# Attenuator.net
KiCad netlist of a schematic drawn in EAGLE
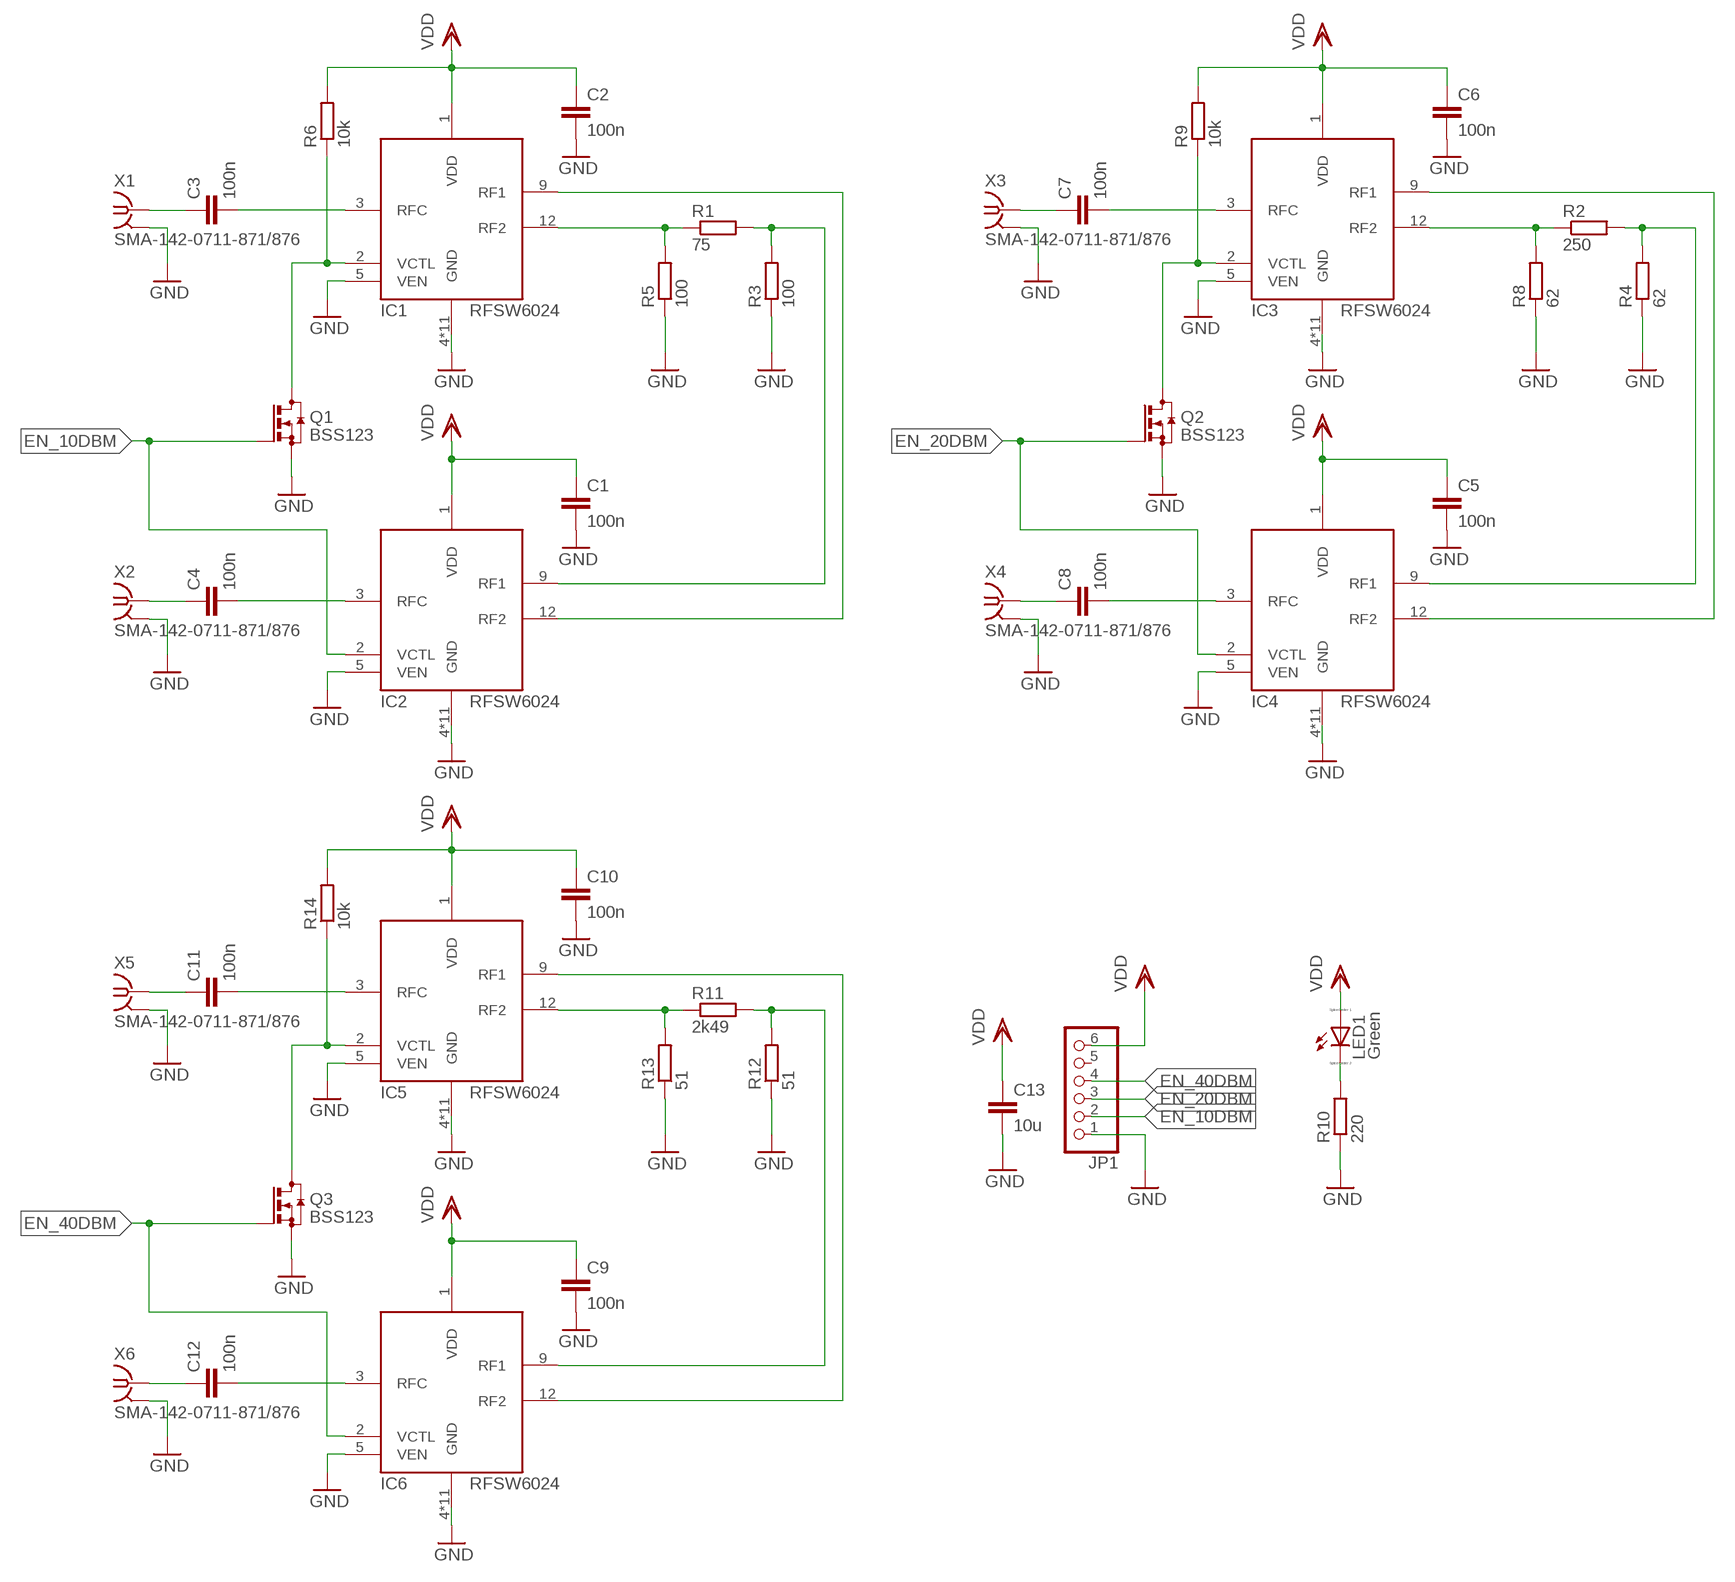
[diagram p0: schematic, sheet 1]

(export (version "E")
  (design (tool "Eeschema 10.0.6"))
  (components
    (comp (ref "C1")
      (value "100n")
      (footprint "eagle-import:C0603K")
      (libsource (lib "eagle-import") (part "rcl_334_C-EUC0603K"))
    )
    (comp (ref "C2")
      (value "100n")
      (footprint "eagle-import:C0603K")
      (libsource (lib "eagle-import") (part "rcl_334_C-EUC0603K"))
    )
    (comp (ref "C3")
      (value "100n")
      (footprint "eagle-import:C0603K")
      (libsource (lib "eagle-import") (part "rcl_334_C-EUC0603K"))
    )
    (comp (ref "C4")
      (value "100n")
      (footprint "eagle-import:C0603K")
      (libsource (lib "eagle-import") (part "rcl_334_C-EUC0603K"))
    )
    (comp (ref "C5")
      (value "100n")
      (footprint "eagle-import:C0603K")
      (libsource (lib "eagle-import") (part "rcl_334_C-EUC0603K"))
    )
    (comp (ref "C6")
      (value "100n")
      (footprint "eagle-import:C0603K")
      (libsource (lib "eagle-import") (part "rcl_334_C-EUC0603K"))
    )
    (comp (ref "C7")
      (value "100n")
      (footprint "eagle-import:C0603K")
      (libsource (lib "eagle-import") (part "rcl_334_C-EUC0603K"))
    )
    (comp (ref "C8")
      (value "100n")
      (footprint "eagle-import:C0603K")
      (libsource (lib "eagle-import") (part "rcl_334_C-EUC0603K"))
    )
    (comp (ref "C9")
      (value "100n")
      (footprint "eagle-import:C0603K")
      (libsource (lib "eagle-import") (part "rcl_334_C-EUC0603K"))
    )
    (comp (ref "C10")
      (value "100n")
      (footprint "eagle-import:C0603K")
      (libsource (lib "eagle-import") (part "rcl_334_C-EUC0603K"))
    )
    (comp (ref "C11")
      (value "100n")
      (footprint "eagle-import:C0603K")
      (libsource (lib "eagle-import") (part "rcl_334_C-EUC0603K"))
    )
    (comp (ref "C12")
      (value "100n")
      (footprint "eagle-import:C0603K")
      (libsource (lib "eagle-import") (part "rcl_334_C-EUC0603K"))
    )
    (comp (ref "C13")
      (value "10u")
      (footprint "eagle-import:C1206")
      (libsource (lib "eagle-import") (part "C-EUC1206"))
    )
    (comp (ref "IC1")
      (value "RFSW6024")
      (footprint "eagle-import:QFN16")
      (libsource (lib "eagle-import") (part "RFSW6024"))
    )
    (comp (ref "IC2")
      (value "RFSW6024")
      (footprint "eagle-import:QFN16")
      (libsource (lib "eagle-import") (part "RFSW6024"))
    )
    (comp (ref "IC3")
      (value "RFSW6024")
      (footprint "eagle-import:QFN16")
      (libsource (lib "eagle-import") (part "RFSW6024"))
    )
    (comp (ref "IC4")
      (value "RFSW6024")
      (footprint "eagle-import:QFN16")
      (libsource (lib "eagle-import") (part "RFSW6024"))
    )
    (comp (ref "IC5")
      (value "RFSW6024")
      (footprint "eagle-import:QFN16")
      (libsource (lib "eagle-import") (part "RFSW6024"))
    )
    (comp (ref "IC6")
      (value "RFSW6024")
      (footprint "eagle-import:QFN16")
      (libsource (lib "eagle-import") (part "RFSW6024"))
    )
    (comp (ref "JP1")
      (value "PINHD-1X6/90")
      (footprint "eagle-import:1X06_90")
      (libsource (lib "eagle-import") (part "PINHD-1X6/90"))
    )
    (comp (ref "LED1")
      (value "Green")
      (footprint "eagle-import:LED_SML0603")
      (libsource (lib "eagle-import") (part "LED_ESML0603"))
    )
    (comp (ref "Q1")
      (value "BSS123")
      (footprint "eagle-import:SOT23")
      (libsource (lib "eagle-import") (part "BSS123"))
    )
    (comp (ref "Q2")
      (value "BSS123")
      (footprint "eagle-import:SOT23")
      (libsource (lib "eagle-import") (part "BSS123"))
    )
    (comp (ref "Q3")
      (value "BSS123")
      (footprint "eagle-import:SOT23")
      (libsource (lib "eagle-import") (part "BSS123"))
    )
    (comp (ref "R1")
      (value "75")
      (footprint "eagle-import:R0603")
      (libsource (lib "eagle-import") (part "resistor_348_R-EU_R0603"))
    )
    (comp (ref "R2")
      (value "250")
      (footprint "eagle-import:R0603")
      (libsource (lib "eagle-import") (part "resistor_348_R-EU_R0603"))
    )
    (comp (ref "R3")
      (value "100")
      (footprint "eagle-import:R0603")
      (libsource (lib "eagle-import") (part "resistor_348_R-EU_R0603"))
    )
    (comp (ref "R4")
      (value "62")
      (footprint "eagle-import:R0603")
      (libsource (lib "eagle-import") (part "resistor_348_R-EU_R0603"))
    )
    (comp (ref "R5")
      (value "100")
      (footprint "eagle-import:R0603")
      (libsource (lib "eagle-import") (part "resistor_348_R-EU_R0603"))
    )
    (comp (ref "R6")
      (value "10k")
      (footprint "eagle-import:R0603")
      (libsource (lib "eagle-import") (part "resistor_348_R-EU_R0603"))
    )
    (comp (ref "R8")
      (value "62")
      (footprint "eagle-import:R0603")
      (libsource (lib "eagle-import") (part "resistor_348_R-EU_R0603"))
    )
    (comp (ref "R9")
      (value "10k")
      (footprint "eagle-import:R0603")
      (libsource (lib "eagle-import") (part "resistor_348_R-EU_R0603"))
    )
    (comp (ref "R10")
      (value "220")
      (footprint "eagle-import:R0603")
      (libsource (lib "eagle-import") (part "R-EU_R0603"))
    )
    (comp (ref "R11")
      (value "2k49")
      (footprint "eagle-import:R0603")
      (libsource (lib "eagle-import") (part "resistor_348_R-EU_R0603"))
    )
    (comp (ref "R12")
      (value "51")
      (footprint "eagle-import:R0603")
      (libsource (lib "eagle-import") (part "resistor_348_R-EU_R0603"))
    )
    (comp (ref "R13")
      (value "51")
      (footprint "eagle-import:R0603")
      (libsource (lib "eagle-import") (part "resistor_348_R-EU_R0603"))
    )
    (comp (ref "R14")
      (value "10k")
      (footprint "eagle-import:R0603")
      (libsource (lib "eagle-import") (part "resistor_348_R-EU_R0603"))
    )
    (comp (ref "X1")
      (value "SMA-142-0711-871/876")
      (footprint "eagle-import:J502-ND-142-0711-871_876")
      (fields (field (name "MF") "JOHNSON COMPONENTS") (field (name "MPN") "142-0711-871"))
      (libsource (lib "eagle-import") (part "SMA-142-0711-871/876"))
    )
    (comp (ref "X2")
      (value "SMA-142-0711-871/876")
      (footprint "eagle-import:J502-ND-142-0711-871_876")
      (fields (field (name "MF") "JOHNSON COMPONENTS") (field (name "MPN") "142-0711-871"))
      (libsource (lib "eagle-import") (part "SMA-142-0711-871/876"))
    )
    (comp (ref "X3")
      (value "SMA-142-0711-871/876")
      (footprint "eagle-import:J502-ND-142-0711-871_876")
      (fields (field (name "MF") "JOHNSON COMPONENTS") (field (name "MPN") "142-0711-871"))
      (libsource (lib "eagle-import") (part "SMA-142-0711-871/876"))
    )
    (comp (ref "X4")
      (value "SMA-142-0711-871/876")
      (footprint "eagle-import:J502-ND-142-0711-871_876")
      (fields (field (name "MF") "JOHNSON COMPONENTS") (field (name "MPN") "142-0711-871"))
      (libsource (lib "eagle-import") (part "SMA-142-0711-871/876"))
    )
    (comp (ref "X5")
      (value "SMA-142-0711-871/876")
      (footprint "eagle-import:J502-ND-142-0711-871_876")
      (fields (field (name "MF") "JOHNSON COMPONENTS") (field (name "MPN") "142-0711-871"))
      (libsource (lib "eagle-import") (part "SMA-142-0711-871/876"))
    )
    (comp (ref "X6")
      (value "SMA-142-0711-871/876")
      (footprint "eagle-import:J502-ND-142-0711-871_876")
      (fields (field (name "MF") "JOHNSON COMPONENTS") (field (name "MPN") "142-0711-871"))
      (libsource (lib "eagle-import") (part "SMA-142-0711-871/876"))
    )
  )
  (nets
    (net (code "1") (name "EN_10DBM") (class "Default")
      (node (ref "IC2") (pin "2") (pinfunction "VCTL_2") (pintype "bidirectional"))
      (node (ref "JP1") (pin "2") (pinfunction "2_2") (pintype "passive"))
      (node (ref "Q1") (pin "1") (pinfunction "G_1") (pintype "passive"))
    )
    (net (code "2") (name "EN_20DBM") (class "Default")
      (node (ref "IC4") (pin "2") (pinfunction "VCTL_2") (pintype "bidirectional"))
      (node (ref "JP1") (pin "3") (pinfunction "3_3") (pintype "passive"))
      (node (ref "Q2") (pin "1") (pinfunction "G_1") (pintype "passive"))
    )
    (net (code "3") (name "EN_40DBM") (class "Default")
      (node (ref "IC6") (pin "2") (pinfunction "VCTL_2") (pintype "bidirectional"))
      (node (ref "JP1") (pin "4") (pinfunction "4_4") (pintype "passive"))
      (node (ref "Q3") (pin "1") (pinfunction "G_1") (pintype "passive"))
    )
    (net (code "4") (name "GND") (class "Default")
      (node (ref "C1") (pin "2") (pinfunction "2_2") (pintype "passive"))
      (node (ref "C10") (pin "2") (pinfunction "2_2") (pintype "passive"))
      (node (ref "C13") (pin "2") (pinfunction "2_2") (pintype "passive"))
      (node (ref "C2") (pin "2") (pinfunction "2_2") (pintype "passive"))
      (node (ref "C5") (pin "2") (pinfunction "2_2") (pintype "passive"))
      (node (ref "C6") (pin "2") (pinfunction "2_2") (pintype "passive"))
      (node (ref "C9") (pin "2") (pinfunction "2_2") (pintype "passive"))
      (node (ref "IC1") (pin "10") (pinfunction "GND_10") (pintype "bidirectional"))
      (node (ref "IC1") (pin "11") (pinfunction "GND_11") (pintype "bidirectional"))
      (node (ref "IC1") (pin "13") (pinfunction "GND_13") (pintype "bidirectional"))
      (node (ref "IC1") (pin "14") (pinfunction "GND_14") (pintype "bidirectional"))
      (node (ref "IC1") (pin "15") (pinfunction "GND_15") (pintype "bidirectional"))
      (node (ref "IC1") (pin "16") (pinfunction "GND_16") (pintype "bidirectional"))
      (node (ref "IC1") (pin "17") (pinfunction "GND_17") (pintype "bidirectional"))
      (node (ref "IC1") (pin "4") (pinfunction "GND_4") (pintype "bidirectional"))
      (node (ref "IC1") (pin "5") (pinfunction "VEN_5") (pintype "bidirectional"))
      (node (ref "IC1") (pin "6") (pinfunction "GND_6") (pintype "bidirectional"))
      (node (ref "IC1") (pin "7") (pinfunction "GND_7") (pintype "bidirectional"))
      (node (ref "IC1") (pin "8") (pinfunction "GND_8") (pintype "bidirectional"))
      (node (ref "IC2") (pin "10") (pinfunction "GND_10") (pintype "bidirectional"))
      (node (ref "IC2") (pin "11") (pinfunction "GND_11") (pintype "bidirectional"))
      (node (ref "IC2") (pin "13") (pinfunction "GND_13") (pintype "bidirectional"))
      (node (ref "IC2") (pin "14") (pinfunction "GND_14") (pintype "bidirectional"))
      (node (ref "IC2") (pin "15") (pinfunction "GND_15") (pintype "bidirectional"))
      (node (ref "IC2") (pin "16") (pinfunction "GND_16") (pintype "bidirectional"))
      (node (ref "IC2") (pin "17") (pinfunction "GND_17") (pintype "bidirectional"))
      (node (ref "IC2") (pin "4") (pinfunction "GND_4") (pintype "bidirectional"))
      (node (ref "IC2") (pin "5") (pinfunction "VEN_5") (pintype "bidirectional"))
      (node (ref "IC2") (pin "6") (pinfunction "GND_6") (pintype "bidirectional"))
      (node (ref "IC2") (pin "7") (pinfunction "GND_7") (pintype "bidirectional"))
      (node (ref "IC2") (pin "8") (pinfunction "GND_8") (pintype "bidirectional"))
      (node (ref "IC3") (pin "10") (pinfunction "GND_10") (pintype "bidirectional"))
      (node (ref "IC3") (pin "11") (pinfunction "GND_11") (pintype "bidirectional"))
      (node (ref "IC3") (pin "13") (pinfunction "GND_13") (pintype "bidirectional"))
      (node (ref "IC3") (pin "14") (pinfunction "GND_14") (pintype "bidirectional"))
      (node (ref "IC3") (pin "15") (pinfunction "GND_15") (pintype "bidirectional"))
      (node (ref "IC3") (pin "16") (pinfunction "GND_16") (pintype "bidirectional"))
      (node (ref "IC3") (pin "17") (pinfunction "GND_17") (pintype "bidirectional"))
      (node (ref "IC3") (pin "4") (pinfunction "GND_4") (pintype "bidirectional"))
      (node (ref "IC3") (pin "5") (pinfunction "VEN_5") (pintype "bidirectional"))
      (node (ref "IC3") (pin "6") (pinfunction "GND_6") (pintype "bidirectional"))
      (node (ref "IC3") (pin "7") (pinfunction "GND_7") (pintype "bidirectional"))
      (node (ref "IC3") (pin "8") (pinfunction "GND_8") (pintype "bidirectional"))
      (node (ref "IC4") (pin "10") (pinfunction "GND_10") (pintype "bidirectional"))
      (node (ref "IC4") (pin "11") (pinfunction "GND_11") (pintype "bidirectional"))
      (node (ref "IC4") (pin "13") (pinfunction "GND_13") (pintype "bidirectional"))
      (node (ref "IC4") (pin "14") (pinfunction "GND_14") (pintype "bidirectional"))
      (node (ref "IC4") (pin "15") (pinfunction "GND_15") (pintype "bidirectional"))
      (node (ref "IC4") (pin "16") (pinfunction "GND_16") (pintype "bidirectional"))
      (node (ref "IC4") (pin "17") (pinfunction "GND_17") (pintype "bidirectional"))
      (node (ref "IC4") (pin "4") (pinfunction "GND_4") (pintype "bidirectional"))
      (node (ref "IC4") (pin "5") (pinfunction "VEN_5") (pintype "bidirectional"))
      (node (ref "IC4") (pin "6") (pinfunction "GND_6") (pintype "bidirectional"))
      (node (ref "IC4") (pin "7") (pinfunction "GND_7") (pintype "bidirectional"))
      (node (ref "IC4") (pin "8") (pinfunction "GND_8") (pintype "bidirectional"))
      (node (ref "IC5") (pin "10") (pinfunction "GND_10") (pintype "bidirectional"))
      (node (ref "IC5") (pin "11") (pinfunction "GND_11") (pintype "bidirectional"))
      (node (ref "IC5") (pin "13") (pinfunction "GND_13") (pintype "bidirectional"))
      (node (ref "IC5") (pin "14") (pinfunction "GND_14") (pintype "bidirectional"))
      (node (ref "IC5") (pin "15") (pinfunction "GND_15") (pintype "bidirectional"))
      (node (ref "IC5") (pin "16") (pinfunction "GND_16") (pintype "bidirectional"))
      (node (ref "IC5") (pin "17") (pinfunction "GND_17") (pintype "bidirectional"))
      (node (ref "IC5") (pin "4") (pinfunction "GND_4") (pintype "bidirectional"))
      (node (ref "IC5") (pin "5") (pinfunction "VEN_5") (pintype "bidirectional"))
      (node (ref "IC5") (pin "6") (pinfunction "GND_6") (pintype "bidirectional"))
      (node (ref "IC5") (pin "7") (pinfunction "GND_7") (pintype "bidirectional"))
      (node (ref "IC5") (pin "8") (pinfunction "GND_8") (pintype "bidirectional"))
      (node (ref "IC6") (pin "10") (pinfunction "GND_10") (pintype "bidirectional"))
      (node (ref "IC6") (pin "11") (pinfunction "GND_11") (pintype "bidirectional"))
      (node (ref "IC6") (pin "13") (pinfunction "GND_13") (pintype "bidirectional"))
      (node (ref "IC6") (pin "14") (pinfunction "GND_14") (pintype "bidirectional"))
      (node (ref "IC6") (pin "15") (pinfunction "GND_15") (pintype "bidirectional"))
      (node (ref "IC6") (pin "16") (pinfunction "GND_16") (pintype "bidirectional"))
      (node (ref "IC6") (pin "17") (pinfunction "GND_17") (pintype "bidirectional"))
      (node (ref "IC6") (pin "4") (pinfunction "GND_4") (pintype "bidirectional"))
      (node (ref "IC6") (pin "5") (pinfunction "VEN_5") (pintype "bidirectional"))
      (node (ref "IC6") (pin "6") (pinfunction "GND_6") (pintype "bidirectional"))
      (node (ref "IC6") (pin "7") (pinfunction "GND_7") (pintype "bidirectional"))
      (node (ref "IC6") (pin "8") (pinfunction "GND_8") (pintype "bidirectional"))
      (node (ref "JP1") (pin "1") (pinfunction "1_1") (pintype "passive"))
      (node (ref "Q1") (pin "2") (pinfunction "S_2") (pintype "passive"))
      (node (ref "Q2") (pin "2") (pinfunction "S_2") (pintype "passive"))
      (node (ref "Q3") (pin "2") (pinfunction "S_2") (pintype "passive"))
      (node (ref "R10") (pin "1") (pinfunction "1_1") (pintype "passive"))
      (node (ref "R12") (pin "1") (pinfunction "1_1") (pintype "passive"))
      (node (ref "R13") (pin "1") (pinfunction "1_1") (pintype "passive"))
      (node (ref "R3") (pin "1") (pinfunction "1_1") (pintype "passive"))
      (node (ref "R4") (pin "1") (pinfunction "1_1") (pintype "passive"))
      (node (ref "R5") (pin "1") (pinfunction "1_1") (pintype "passive"))
      (node (ref "R8") (pin "1") (pinfunction "1_1") (pintype "passive"))
      (node (ref "X1") (pin "G@1") (pinfunction "2_G@1") (pintype "passive"))
      (node (ref "X1") (pin "G@2") (pinfunction "2_G@2") (pintype "passive"))
      (node (ref "X1") (pin "G@3") (pinfunction "2_G@3") (pintype "passive"))
      (node (ref "X1") (pin "G@4") (pinfunction "2_G@4") (pintype "passive"))
      (node (ref "X2") (pin "G@1") (pinfunction "2_G@1") (pintype "passive"))
      (node (ref "X2") (pin "G@2") (pinfunction "2_G@2") (pintype "passive"))
      (node (ref "X2") (pin "G@3") (pinfunction "2_G@3") (pintype "passive"))
      (node (ref "X2") (pin "G@4") (pinfunction "2_G@4") (pintype "passive"))
      (node (ref "X3") (pin "G@1") (pinfunction "2_G@1") (pintype "passive"))
      (node (ref "X3") (pin "G@2") (pinfunction "2_G@2") (pintype "passive"))
      (node (ref "X3") (pin "G@3") (pinfunction "2_G@3") (pintype "passive"))
      (node (ref "X3") (pin "G@4") (pinfunction "2_G@4") (pintype "passive"))
      (node (ref "X4") (pin "G@1") (pinfunction "2_G@1") (pintype "passive"))
      (node (ref "X4") (pin "G@2") (pinfunction "2_G@2") (pintype "passive"))
      (node (ref "X4") (pin "G@3") (pinfunction "2_G@3") (pintype "passive"))
      (node (ref "X4") (pin "G@4") (pinfunction "2_G@4") (pintype "passive"))
      (node (ref "X5") (pin "G@1") (pinfunction "2_G@1") (pintype "passive"))
      (node (ref "X5") (pin "G@2") (pinfunction "2_G@2") (pintype "passive"))
      (node (ref "X5") (pin "G@3") (pinfunction "2_G@3") (pintype "passive"))
      (node (ref "X5") (pin "G@4") (pinfunction "2_G@4") (pintype "passive"))
      (node (ref "X6") (pin "G@1") (pinfunction "2_G@1") (pintype "passive"))
      (node (ref "X6") (pin "G@2") (pinfunction "2_G@2") (pintype "passive"))
      (node (ref "X6") (pin "G@3") (pinfunction "2_G@3") (pintype "passive"))
      (node (ref "X6") (pin "G@4") (pinfunction "2_G@4") (pintype "passive"))
    )
    (net (code "5") (name "Net-(C3-Pad1)") (class "Default")
      (node (ref "C3") (pin "1") (pinfunction "1_1") (pintype "passive"))
      (node (ref "X1") (pin "1") (pinfunction "1_1") (pintype "passive"))
    )
    (net (code "6") (name "Net-(C4-Pad1)") (class "Default")
      (node (ref "C4") (pin "1") (pinfunction "1_1") (pintype "passive"))
      (node (ref "X2") (pin "1") (pinfunction "1_1") (pintype "passive"))
    )
    (net (code "7") (name "Net-(C7-Pad1)") (class "Default")
      (node (ref "C7") (pin "1") (pinfunction "1_1") (pintype "passive"))
      (node (ref "X3") (pin "1") (pinfunction "1_1") (pintype "passive"))
    )
    (net (code "8") (name "Net-(C8-Pad1)") (class "Default")
      (node (ref "C8") (pin "1") (pinfunction "1_1") (pintype "passive"))
      (node (ref "X4") (pin "1") (pinfunction "1_1") (pintype "passive"))
    )
    (net (code "9") (name "Net-(C11-Pad1)") (class "Default")
      (node (ref "C11") (pin "1") (pinfunction "1_1") (pintype "passive"))
      (node (ref "X5") (pin "1") (pinfunction "1_1") (pintype "passive"))
    )
    (net (code "10") (name "Net-(C12-Pad1)") (class "Default")
      (node (ref "C12") (pin "1") (pinfunction "1_1") (pintype "passive"))
      (node (ref "X6") (pin "1") (pinfunction "1_1") (pintype "passive"))
    )
    (net (code "11") (name "Net-(IC1-RF1)") (class "Default")
      (node (ref "IC1") (pin "9") (pinfunction "RF1_9") (pintype "bidirectional"))
      (node (ref "IC2") (pin "12") (pinfunction "RF2_12") (pintype "bidirectional"))
    )
    (net (code "12") (name "Net-(IC1-RF2)") (class "Default")
      (node (ref "IC1") (pin "12") (pinfunction "RF2_12") (pintype "bidirectional"))
      (node (ref "R1") (pin "1") (pinfunction "1_1") (pintype "passive"))
      (node (ref "R5") (pin "2") (pinfunction "2_2") (pintype "passive"))
    )
    (net (code "13") (name "Net-(IC1-RFC)") (class "Default")
      (node (ref "C3") (pin "2") (pinfunction "2_2") (pintype "passive"))
      (node (ref "IC1") (pin "3") (pinfunction "RFC_3") (pintype "bidirectional"))
    )
    (net (code "14") (name "Net-(IC1-VCTL)") (class "Default")
      (node (ref "IC1") (pin "2") (pinfunction "VCTL_2") (pintype "bidirectional"))
      (node (ref "Q1") (pin "3") (pinfunction "D_3") (pintype "passive"))
      (node (ref "R6") (pin "1") (pinfunction "1_1") (pintype "passive"))
    )
    (net (code "15") (name "Net-(IC2-RF1)") (class "Default")
      (node (ref "IC2") (pin "9") (pinfunction "RF1_9") (pintype "bidirectional"))
      (node (ref "R1") (pin "2") (pinfunction "2_2") (pintype "passive"))
      (node (ref "R3") (pin "2") (pinfunction "2_2") (pintype "passive"))
    )
    (net (code "16") (name "Net-(IC2-RFC)") (class "Default")
      (node (ref "C4") (pin "2") (pinfunction "2_2") (pintype "passive"))
      (node (ref "IC2") (pin "3") (pinfunction "RFC_3") (pintype "bidirectional"))
    )
    (net (code "17") (name "Net-(IC3-RF1)") (class "Default")
      (node (ref "IC3") (pin "9") (pinfunction "RF1_9") (pintype "bidirectional"))
      (node (ref "IC4") (pin "12") (pinfunction "RF2_12") (pintype "bidirectional"))
    )
    (net (code "18") (name "Net-(IC3-RF2)") (class "Default")
      (node (ref "IC3") (pin "12") (pinfunction "RF2_12") (pintype "bidirectional"))
      (node (ref "R2") (pin "1") (pinfunction "1_1") (pintype "passive"))
      (node (ref "R8") (pin "2") (pinfunction "2_2") (pintype "passive"))
    )
    (net (code "19") (name "Net-(IC3-RFC)") (class "Default")
      (node (ref "C7") (pin "2") (pinfunction "2_2") (pintype "passive"))
      (node (ref "IC3") (pin "3") (pinfunction "RFC_3") (pintype "bidirectional"))
    )
    (net (code "20") (name "Net-(IC3-VCTL)") (class "Default")
      (node (ref "IC3") (pin "2") (pinfunction "VCTL_2") (pintype "bidirectional"))
      (node (ref "Q2") (pin "3") (pinfunction "D_3") (pintype "passive"))
      (node (ref "R9") (pin "1") (pinfunction "1_1") (pintype "passive"))
    )
    (net (code "21") (name "Net-(IC4-RF1)") (class "Default")
      (node (ref "IC4") (pin "9") (pinfunction "RF1_9") (pintype "bidirectional"))
      (node (ref "R2") (pin "2") (pinfunction "2_2") (pintype "passive"))
      (node (ref "R4") (pin "2") (pinfunction "2_2") (pintype "passive"))
    )
    (net (code "22") (name "Net-(IC4-RFC)") (class "Default")
      (node (ref "C8") (pin "2") (pinfunction "2_2") (pintype "passive"))
      (node (ref "IC4") (pin "3") (pinfunction "RFC_3") (pintype "bidirectional"))
    )
    (net (code "23") (name "Net-(IC5-RF1)") (class "Default")
      (node (ref "IC5") (pin "9") (pinfunction "RF1_9") (pintype "bidirectional"))
      (node (ref "IC6") (pin "12") (pinfunction "RF2_12") (pintype "bidirectional"))
    )
    (net (code "24") (name "Net-(IC5-RF2)") (class "Default")
      (node (ref "IC5") (pin "12") (pinfunction "RF2_12") (pintype "bidirectional"))
      (node (ref "R11") (pin "1") (pinfunction "1_1") (pintype "passive"))
      (node (ref "R13") (pin "2") (pinfunction "2_2") (pintype "passive"))
    )
    (net (code "25") (name "Net-(IC5-RFC)") (class "Default")
      (node (ref "C11") (pin "2") (pinfunction "2_2") (pintype "passive"))
      (node (ref "IC5") (pin "3") (pinfunction "RFC_3") (pintype "bidirectional"))
    )
    (net (code "26") (name "Net-(IC5-VCTL)") (class "Default")
      (node (ref "IC5") (pin "2") (pinfunction "VCTL_2") (pintype "bidirectional"))
      (node (ref "Q3") (pin "3") (pinfunction "D_3") (pintype "passive"))
      (node (ref "R14") (pin "1") (pinfunction "1_1") (pintype "passive"))
    )
    (net (code "27") (name "Net-(IC6-RF1)") (class "Default")
      (node (ref "IC6") (pin "9") (pinfunction "RF1_9") (pintype "bidirectional"))
      (node (ref "R11") (pin "2") (pinfunction "2_2") (pintype "passive"))
      (node (ref "R12") (pin "2") (pinfunction "2_2") (pintype "passive"))
    )
    (net (code "28") (name "Net-(IC6-RFC)") (class "Default")
      (node (ref "C12") (pin "2") (pinfunction "2_2") (pintype "passive"))
      (node (ref "IC6") (pin "3") (pinfunction "RFC_3") (pintype "bidirectional"))
    )
    (net (code "29") (name "Net-(LED1-PadC)") (class "Default")
      (node (ref "LED1") (pin "C") (pinfunction "C_C") (pintype "passive"))
      (node (ref "R10") (pin "2") (pinfunction "2_2") (pintype "passive"))
    )
    (net (code "30") (name "VDD") (class "Default")
      (node (ref "C1") (pin "1") (pinfunction "1_1") (pintype "passive"))
      (node (ref "C10") (pin "1") (pinfunction "1_1") (pintype "passive"))
      (node (ref "C13") (pin "1") (pinfunction "1_1") (pintype "passive"))
      (node (ref "C2") (pin "1") (pinfunction "1_1") (pintype "passive"))
      (node (ref "C5") (pin "1") (pinfunction "1_1") (pintype "passive"))
      (node (ref "C6") (pin "1") (pinfunction "1_1") (pintype "passive"))
      (node (ref "C9") (pin "1") (pinfunction "1_1") (pintype "passive"))
      (node (ref "IC1") (pin "1") (pinfunction "VDD_1") (pintype "bidirectional"))
      (node (ref "IC2") (pin "1") (pinfunction "VDD_1") (pintype "bidirectional"))
      (node (ref "IC3") (pin "1") (pinfunction "VDD_1") (pintype "bidirectional"))
      (node (ref "IC4") (pin "1") (pinfunction "VDD_1") (pintype "bidirectional"))
      (node (ref "IC5") (pin "1") (pinfunction "VDD_1") (pintype "bidirectional"))
      (node (ref "IC6") (pin "1") (pinfunction "VDD_1") (pintype "bidirectional"))
      (node (ref "JP1") (pin "6") (pinfunction "6_6") (pintype "passive"))
      (node (ref "LED1") (pin "A") (pinfunction "A_A") (pintype "passive"))
      (node (ref "R14") (pin "2") (pinfunction "2_2") (pintype "passive"))
      (node (ref "R6") (pin "2") (pinfunction "2_2") (pintype "passive"))
      (node (ref "R9") (pin "2") (pinfunction "2_2") (pintype "passive"))
    )
    (net (code "31") (name "unconnected-(JP1-Pad5)") (class "Default")
      (node (ref "JP1") (pin "5") (pinfunction "5_5") (pintype "passive"))
    )
  )
)
